# Addon-mapleCUx_HM-RFM69-RFM95-V10-016.net
KiCad netlist of a schematic drawn in EAGLE
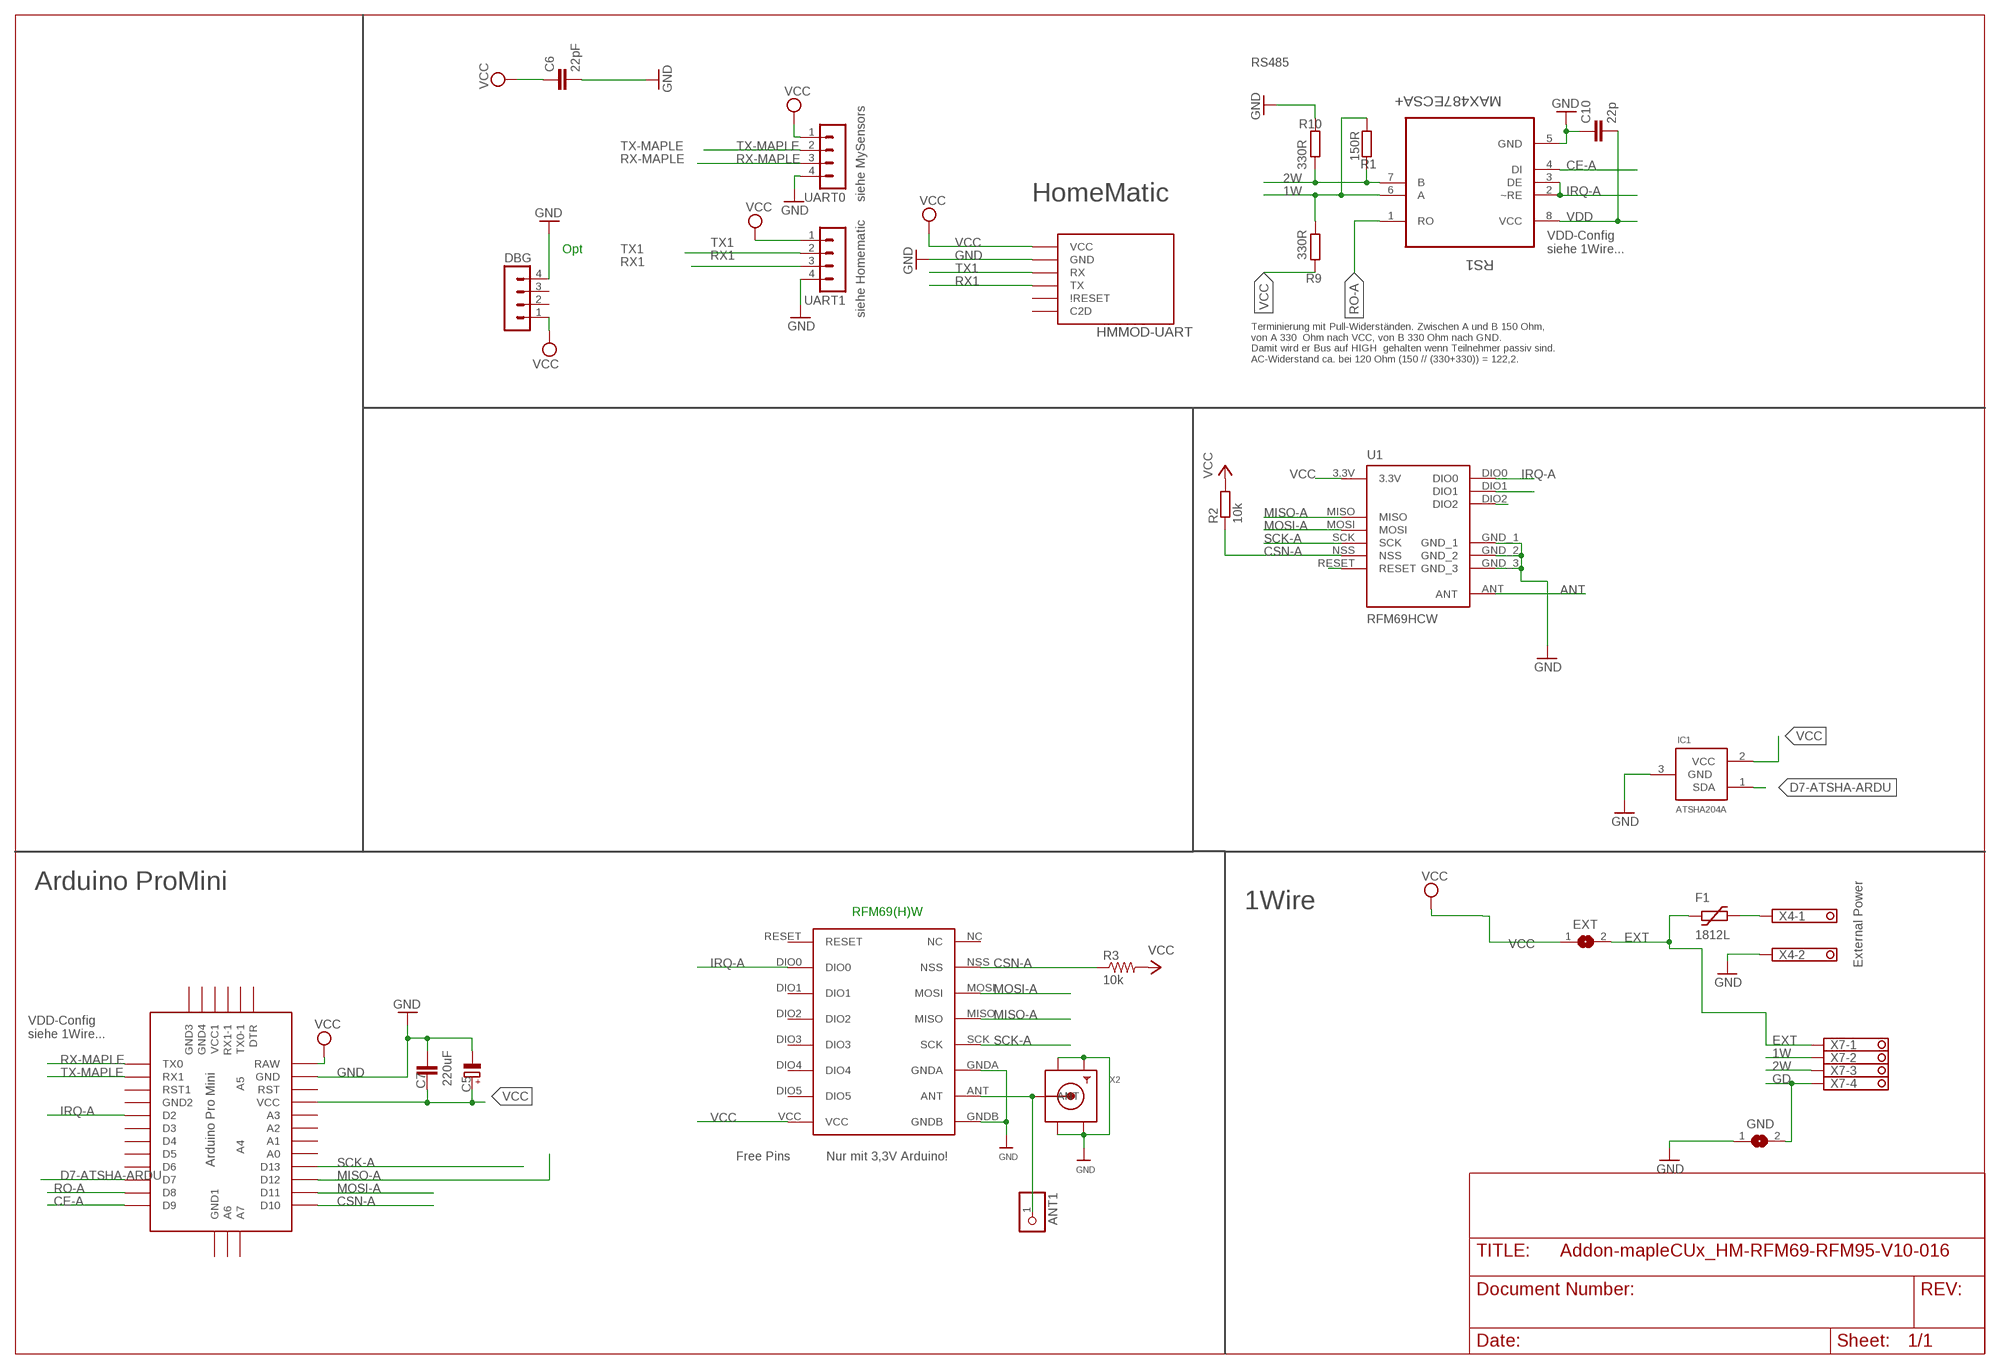
[diagram p0: schematic, sheet 1]

(export (version "E")
  (design (tool "Eeschema 10.0.6"))
  (components
    (comp (ref "ANT1")
      (value "PINHD-1X1")
      (footprint "eagle-import:1X01")
      (libsource (lib "eagle-import") (part "PINHD-1X1"))
    )
    (comp (ref "C5")
      (value "220uF")
      (footprint "eagle-import:E5-8,5")
      (libsource (lib "eagle-import") (part "CPOL-EUE5-8.5"))
    )
    (comp (ref "C6")
      (value "22pF")
      (footprint "eagle-import:C0805")
      (libsource (lib "eagle-import") (part "C-EUC0805"))
    )
    (comp (ref "C7")
      (value "C-EUC1812")
      (footprint "eagle-import:C1812")
      (libsource (lib "eagle-import") (part "C-EUC1812"))
    )
    (comp (ref "C10")
      (value "22p")
      (footprint "eagle-import:C0805")
      (libsource (lib "eagle-import") (part "C-EUC0805"))
    )
    (comp (ref "DBG")
      (value "MA04-1")
      (footprint "eagle-import:MA04-1")
      (libsource (lib "eagle-import") (part "MA04-1"))
    )
    (comp (ref "EXT") (value "SJ") (footprint "eagle-import:SJ") (libsource (lib "eagle-import") (part "SJ")))
    (comp (ref "F1")
      (value "1812L")
      (footprint "eagle-import:1812L")
      (libsource (lib "eagle-import") (part "1812L"))
    )
    (comp (ref "GND") (value "SJ") (footprint "eagle-import:SJ") (libsource (lib "eagle-import") (part "SJ")))
    (comp (ref "HMMOD-UART")
      (value "HM-MOD-UARTDIL")
      (footprint "eagle-import:HM-MOD-UART-DIL")
      (libsource (lib "eagle-import") (part "HM-MOD-UARTDIL"))
    )
    (comp (ref "IC1")
      (value "ATSHA204A")
      (footprint "eagle-import:SOT23")
      (libsource (lib "eagle-import") (part "ATSHA204A"))
    )
    (comp (ref "R1")
      (value "150R")
      (footprint "eagle-import:R0805")
      (libsource (lib "eagle-import") (part "R-EU_R0805"))
    )
    (comp (ref "R2")
      (value "10k")
      (footprint "eagle-import:M0805")
      (libsource (lib "eagle-import") (part "R-EU_M0805"))
    )
    (comp (ref "R3")
      (value "10k")
      (footprint "eagle-import:0805")
      (libsource (lib "eagle-import") (part "RESISTOR0805-RES"))
    )
    (comp (ref "R9")
      (value "330R")
      (footprint "eagle-import:R0805")
      (libsource (lib "eagle-import") (part "R-EU_R0805"))
    )
    (comp (ref "R10")
      (value "330R")
      (footprint "eagle-import:R0805")
      (libsource (lib "eagle-import") (part "R-EU_R0805"))
    )
    (comp (ref "RFM69W")
      (value "RFM69HW")
      (footprint "eagle-import:RFM")
      (libsource (lib "eagle-import") (part "RFM69HW"))
    )
    (comp (ref "RS1")
      (value "MAX487ECSA+")
      (footprint "eagle-import:SOIC127P600X175-8N")
      (libsource (lib "eagle-import") (part "MAX487ECSA+"))
    )
    (comp (ref "U$2")
      (value "ABK-PRO-MINI")
      (footprint "eagle-import:ABK-PRO-MINI")
      (libsource (lib "eagle-import") (part "ABK-PRO-MINI"))
    )
    (comp (ref "U1")
      (value "RFM69HCW")
      (footprint "eagle-import:RFM69HCW-XXXS2")
      (libsource (lib "eagle-import") (part "RFM69HCW"))
    )
    (comp (ref "UART0")
      (value "MA04-1")
      (footprint "eagle-import:MA04-1")
      (libsource (lib "eagle-import") (part "MA04-1"))
    )
    (comp (ref "UART1")
      (value "MA04-1")
      (footprint "eagle-import:MA04-1")
      (libsource (lib "eagle-import") (part "MA04-1"))
    )
    (comp (ref "X2")
      (value "SMACONNECTOR_EDGE")
      (footprint "eagle-import:SMA_EDGELAUNCH")
      (libsource (lib "eagle-import") (part "SMACONNECTOR_EDGE"))
    )
    (comp (ref "X4")
      (value "1751248")
      (footprint "eagle-import:1751248")
      (libsource (lib "eagle-import") (part "1751248"))
    )
    (comp (ref "X7")
      (value "1751264")
      (footprint "eagle-import:1751264")
      (libsource (lib "eagle-import") (part "1751264"))
    )
  )
  (nets
    (net (code "1") (name "/1W") (class "Default")
      (node (ref "R1") (pin "1") (pinfunction "1_1") (pintype "passive"))
      (node (ref "R9") (pin "2") (pinfunction "2_2") (pintype "passive"))
      (node (ref "RS1") (pin "6") (pinfunction "A_6") (pintype "bidirectional"))
      (node (ref "X7") (pin "2") (pinfunction "K_2") (pintype "passive"))
    )
    (net (code "2") (name "/2W") (class "Default")
      (node (ref "R1") (pin "2") (pinfunction "2_2") (pintype "passive"))
      (node (ref "R10") (pin "1") (pinfunction "1_1") (pintype "passive"))
      (node (ref "RS1") (pin "7") (pinfunction "B_7") (pintype "bidirectional"))
      (node (ref "X7") (pin "3") (pinfunction "K_3") (pintype "passive"))
    )
    (net (code "3") (name "/ANT") (class "Default")
      (node (ref "ANT1") (pin "1") (pinfunction "1_1") (pintype "passive"))
      (node (ref "RFM69W") (pin "ANT") (pinfunction "ANT_ANT") (pintype "bidirectional"))
      (node (ref "U1") (pin "ANT") (pinfunction "ANT_ANT") (pintype "passive"))
      (node (ref "X2") (pin "P") (pinfunction "ANT_P") (pintype "bidirectional"))
    )
    (net (code "4") (name "/CE-A") (class "Default")
      (node (ref "RS1") (pin "4") (pinfunction "DI_4") (pintype "input"))
      (node (ref "U$2") (pin "D9") (pinfunction "D9_D9") (pintype "bidirectional"))
    )
    (net (code "5") (name "/CSN-A") (class "Default")
      (node (ref "R2") (pin "1") (pinfunction "1_1") (pintype "passive"))
      (node (ref "R3") (pin "1") (pinfunction "1_1") (pintype "passive"))
      (node (ref "RFM69W") (pin "NSS") (pinfunction "NSS_NSS") (pintype "bidirectional"))
      (node (ref "U$2") (pin "D10") (pinfunction "D10_D10") (pintype "bidirectional"))
      (node (ref "U1") (pin "NSS") (pinfunction "NSS_NSS") (pintype "input"))
    )
    (net (code "6") (name "/EXT") (class "Default")
      (node (ref "EXT") (pin "2") (pinfunction "2_2") (pintype "passive"))
      (node (ref "F1") (pin "P$1") (pinfunction "1_P$1") (pintype "passive"))
      (node (ref "X7") (pin "1") (pinfunction "K_1") (pintype "passive"))
    )
    (net (code "7") (name "/GD") (class "Default")
      (node (ref "GND") (pin "2") (pinfunction "2_2") (pintype "passive"))
      (node (ref "X7") (pin "4") (pinfunction "K_4") (pintype "passive"))
    )
    (net (code "8") (name "/IRQ-A") (class "Default")
      (node (ref "RFM69W") (pin "DIO0") (pinfunction "DIO0_DIO0") (pintype "bidirectional"))
      (node (ref "RS1") (pin "2") (pinfunction "~{RE}_2") (pintype "input"))
      (node (ref "RS1") (pin "3") (pinfunction "DE_3") (pintype "input"))
      (node (ref "U$2") (pin "D2") (pinfunction "D2_D2") (pintype "bidirectional"))
      (node (ref "U1") (pin "DIO0") (pinfunction "DIO0_DIO0") (pintype "bidirectional"))
    )
    (net (code "9") (name "/MISO-A") (class "Default")
      (node (ref "RFM69W") (pin "MISO") (pinfunction "MISO_MISO") (pintype "bidirectional"))
      (node (ref "U$2") (pin "D12") (pinfunction "D12_D12") (pintype "bidirectional"))
      (node (ref "U1") (pin "MISO") (pinfunction "MISO_MISO") (pintype "bidirectional"))
    )
    (net (code "10") (name "/MOSI-A") (class "Default")
      (node (ref "RFM69W") (pin "MOSI") (pinfunction "MOSI_MOSI") (pintype "bidirectional"))
      (node (ref "U$2") (pin "D11") (pinfunction "D11_D11") (pintype "bidirectional"))
      (node (ref "U1") (pin "MOSI") (pinfunction "MOSI_MOSI") (pintype "input"))
    )
    (net (code "11") (name "/RX-MAPLE") (class "Default")
      (node (ref "U$2") (pin "TX0") (pinfunction "TX0_TX0") (pintype "bidirectional"))
      (node (ref "UART0") (pin "3") (pinfunction "3_3") (pintype "passive"))
    )
    (net (code "12") (name "/RX1") (class "Default")
      (node (ref "HMMOD-UART") (pin "5") (pinfunction "TX_5") (pintype "bidirectional"))
      (node (ref "UART1") (pin "3") (pinfunction "3_3") (pintype "passive"))
    )
    (net (code "13") (name "/SCK-A") (class "Default")
      (node (ref "RFM69W") (pin "SCK") (pinfunction "SCK_SCK") (pintype "bidirectional"))
      (node (ref "U$2") (pin "D13") (pinfunction "D13_D13") (pintype "bidirectional"))
      (node (ref "U1") (pin "SCK") (pinfunction "SCK_SCK") (pintype "input"))
    )
    (net (code "14") (name "/TX-MAPLE") (class "Default")
      (node (ref "U$2") (pin "RX1") (pinfunction "RX1_RX1") (pintype "bidirectional"))
      (node (ref "UART0") (pin "2") (pinfunction "2_2") (pintype "passive"))
    )
    (net (code "15") (name "/TX1") (class "Default")
      (node (ref "HMMOD-UART") (pin "6") (pinfunction "RX_6") (pintype "bidirectional"))
      (node (ref "UART1") (pin "2") (pinfunction "2_2") (pintype "passive"))
    )
    (net (code "16") (name "/VDD") (class "Default")
      (node (ref "C10") (pin "2") (pinfunction "2_2") (pintype "passive"))
      (node (ref "RS1") (pin "8") (pinfunction "VCC_8") (pintype "power_in"))
    )
    (net (code "17") (name "D7-ATSHA-ARDU") (class "Default")
      (node (ref "IC1") (pin "1") (pinfunction "SDA_1") (pintype "bidirectional"))
      (node (ref "U$2") (pin "D7") (pinfunction "D7_D7") (pintype "bidirectional"))
    )
    (net (code "18") (name "GND") (class "Default")
      (node (ref "C10") (pin "1") (pinfunction "1_1") (pintype "passive"))
      (node (ref "C5") (pin "-") (pinfunction "-_-") (pintype "passive"))
      (node (ref "C6") (pin "2") (pinfunction "2_2") (pintype "passive"))
      (node (ref "C7") (pin "1") (pinfunction "1_1") (pintype "passive"))
      (node (ref "DBG") (pin "4") (pinfunction "4_4") (pintype "passive"))
      (node (ref "GND") (pin "1") (pinfunction "1_1") (pintype "passive"))
      (node (ref "HMMOD-UART") (pin "2") (pinfunction "GND_2") (pintype "power_in"))
      (node (ref "IC1") (pin "3") (pinfunction "GND_3") (pintype "bidirectional"))
      (node (ref "R10") (pin "2") (pinfunction "2_2") (pintype "passive"))
      (node (ref "RFM69W") (pin "GNDA") (pinfunction "GNDA_GNDA") (pintype "bidirectional"))
      (node (ref "RFM69W") (pin "GNDB") (pinfunction "GNDB_GNDB") (pintype "bidirectional"))
      (node (ref "RS1") (pin "5") (pinfunction "GND_5") (pintype "passive"))
      (node (ref "U$2") (pin "GND") (pinfunction "GND_GND") (pintype "bidirectional"))
      (node (ref "U1") (pin "GND_1") (pinfunction "GND_1_GND_1") (pintype "power_in"))
      (node (ref "U1") (pin "GND_2") (pinfunction "GND_2_GND_2") (pintype "power_in"))
      (node (ref "U1") (pin "GND_3") (pinfunction "GND_3_GND_3") (pintype "power_in"))
      (node (ref "UART0") (pin "4") (pinfunction "4_4") (pintype "passive"))
      (node (ref "UART1") (pin "4") (pinfunction "4_4") (pintype "passive"))
      (node (ref "X2") (pin "GND@1") (pinfunction "GND4_GND@1") (pintype "power_in"))
      (node (ref "X2") (pin "GND@2") (pinfunction "GND3_GND@2") (pintype "power_in"))
      (node (ref "X2") (pin "GND@3") (pinfunction "GND2_GND@3") (pintype "power_in"))
      (node (ref "X2") (pin "GND@4") (pinfunction "GND1_GND@4") (pintype "power_in"))
      (node (ref "X4") (pin "2") (pinfunction "K_2") (pintype "passive"))
    )
    (net (code "19") (name "Net-(F1-2)") (class "Default")
      (node (ref "F1") (pin "P$2") (pinfunction "2_P$2") (pintype "passive"))
      (node (ref "X4") (pin "1") (pinfunction "K_1") (pintype "passive"))
    )
    (net (code "20") (name "RO-A") (class "Default")
      (node (ref "RS1") (pin "1") (pinfunction "RO_1") (pintype "output"))
      (node (ref "U$2") (pin "D8") (pinfunction "D8_D8") (pintype "bidirectional"))
    )
    (net (code "21") (name "VCC") (class "Default")
      (node (ref "C5") (pin "+") (pinfunction "+_+") (pintype "passive"))
      (node (ref "C6") (pin "1") (pinfunction "1_1") (pintype "passive"))
      (node (ref "C7") (pin "2") (pinfunction "2_2") (pintype "passive"))
      (node (ref "DBG") (pin "1") (pinfunction "1_1") (pintype "passive"))
      (node (ref "EXT") (pin "1") (pinfunction "1_1") (pintype "passive"))
      (node (ref "HMMOD-UART") (pin "1") (pinfunction "VCC_1") (pintype "power_in"))
      (node (ref "IC1") (pin "2") (pinfunction "VCC_2") (pintype "bidirectional"))
      (node (ref "R2") (pin "2") (pinfunction "2_2") (pintype "passive"))
      (node (ref "R3") (pin "2") (pinfunction "2_2") (pintype "passive"))
      (node (ref "R9") (pin "1") (pinfunction "1_1") (pintype "passive"))
      (node (ref "RFM69W") (pin "VCC") (pinfunction "VCC_VCC") (pintype "bidirectional"))
      (node (ref "U$2") (pin "RAW") (pinfunction "RAW_RAW") (pintype "bidirectional"))
      (node (ref "U$2") (pin "VCC") (pinfunction "VCC_VCC") (pintype "bidirectional"))
      (node (ref "U1") (pin "3.3V") (pinfunction "3.3V_3.3V") (pintype "power_in"))
      (node (ref "UART0") (pin "1") (pinfunction "1_1") (pintype "passive"))
      (node (ref "UART1") (pin "1") (pinfunction "1_1") (pintype "passive"))
    )
    (net (code "22") (name "unconnected-(DBG-Pad2)") (class "Default")
      (node (ref "DBG") (pin "2") (pinfunction "2_2") (pintype "passive"))
    )
    (net (code "23") (name "unconnected-(DBG-Pad3)") (class "Default")
      (node (ref "DBG") (pin "3") (pinfunction "3_3") (pintype "passive"))
    )
    (net (code "24") (name "unconnected-(HMMOD-UART-C2D-Pad3)") (class "Default")
      (node (ref "HMMOD-UART") (pin "3") (pinfunction "C2D_3") (pintype "bidirectional"))
    )
    (net (code "25") (name "unconnected-(HMMOD-UART-\\~{RESET}-Pad4)") (class "Default")
      (node (ref "HMMOD-UART") (pin "4") (pinfunction "\\~{RESET}_4") (pintype "bidirectional"))
    )
    (net (code "26") (name "unconnected-(RFM69W-PadDIO1)") (class "Default")
      (node (ref "RFM69W") (pin "DIO1") (pinfunction "DIO1_DIO1") (pintype "bidirectional"))
    )
    (net (code "27") (name "unconnected-(RFM69W-PadDIO2)") (class "Default")
      (node (ref "RFM69W") (pin "DIO2") (pinfunction "DIO2_DIO2") (pintype "bidirectional"))
    )
    (net (code "28") (name "unconnected-(RFM69W-PadDIO3)") (class "Default")
      (node (ref "RFM69W") (pin "DIO3") (pinfunction "DIO3_DIO3") (pintype "bidirectional"))
    )
    (net (code "29") (name "unconnected-(RFM69W-PadDIO4)") (class "Default")
      (node (ref "RFM69W") (pin "DIO4") (pinfunction "DIO4_DIO4") (pintype "bidirectional"))
    )
    (net (code "30") (name "unconnected-(RFM69W-PadDIO5)") (class "Default")
      (node (ref "RFM69W") (pin "DIO5") (pinfunction "DIO5_DIO5") (pintype "bidirectional"))
    )
    (net (code "31") (name "unconnected-(RFM69W-PadNC)") (class "Default")
      (node (ref "RFM69W") (pin "NC") (pinfunction "NC_NC") (pintype "bidirectional"))
    )
    (net (code "32") (name "unconnected-(RFM69W-PadRESET)") (class "Default")
      (node (ref "RFM69W") (pin "RESET") (pinfunction "RESET_RESET") (pintype "bidirectional"))
    )
    (net (code "33") (name "unconnected-(U$2-GND1-PadGND4)") (class "Default")
      (node (ref "U$2") (pin "GND4") (pinfunction "GND1_GND4") (pintype "bidirectional"))
    )
    (net (code "34") (name "unconnected-(U$2-GND2-PadGND1)") (class "Default")
      (node (ref "U$2") (pin "GND1") (pinfunction "GND2_GND1") (pintype "bidirectional"))
    )
    (net (code "35") (name "unconnected-(U$2-GND3-PadGND2)") (class "Default")
      (node (ref "U$2") (pin "GND2") (pinfunction "GND3_GND2") (pintype "bidirectional"))
    )
    (net (code "36") (name "unconnected-(U$2-GND4-PadGND3)") (class "Default")
      (node (ref "U$2") (pin "GND3") (pinfunction "GND4_GND3") (pintype "bidirectional"))
    )
    (net (code "37") (name "unconnected-(U$2-PadA0)") (class "Default")
      (node (ref "U$2") (pin "A0") (pinfunction "A0_A0") (pintype "bidirectional"))
    )
    (net (code "38") (name "unconnected-(U$2-PadA1)") (class "Default")
      (node (ref "U$2") (pin "A1") (pinfunction "A1_A1") (pintype "bidirectional"))
    )
    (net (code "39") (name "unconnected-(U$2-PadA2)") (class "Default")
      (node (ref "U$2") (pin "A2") (pinfunction "A2_A2") (pintype "bidirectional"))
    )
    (net (code "40") (name "unconnected-(U$2-PadA3)") (class "Default")
      (node (ref "U$2") (pin "A3") (pinfunction "A3_A3") (pintype "bidirectional"))
    )
    (net (code "41") (name "unconnected-(U$2-PadA4)") (class "Default")
      (node (ref "U$2") (pin "A4") (pinfunction "A4_A4") (pintype "bidirectional"))
    )
    (net (code "42") (name "unconnected-(U$2-PadA5)") (class "Default")
      (node (ref "U$2") (pin "A5") (pinfunction "A5_A5") (pintype "bidirectional"))
    )
    (net (code "43") (name "unconnected-(U$2-PadA6)") (class "Default")
      (node (ref "U$2") (pin "A6") (pinfunction "A6_A6") (pintype "bidirectional"))
    )
    (net (code "44") (name "unconnected-(U$2-PadA7)") (class "Default")
      (node (ref "U$2") (pin "A7") (pinfunction "A7_A7") (pintype "bidirectional"))
    )
    (net (code "45") (name "unconnected-(U$2-PadD3)") (class "Default")
      (node (ref "U$2") (pin "D3") (pinfunction "D3_D3") (pintype "bidirectional"))
    )
    (net (code "46") (name "unconnected-(U$2-PadD4)") (class "Default")
      (node (ref "U$2") (pin "D4") (pinfunction "D4_D4") (pintype "bidirectional"))
    )
    (net (code "47") (name "unconnected-(U$2-PadD5)") (class "Default")
      (node (ref "U$2") (pin "D5") (pinfunction "D5_D5") (pintype "bidirectional"))
    )
    (net (code "48") (name "unconnected-(U$2-PadD6)") (class "Default")
      (node (ref "U$2") (pin "D6") (pinfunction "D6_D6") (pintype "bidirectional"))
    )
    (net (code "49") (name "unconnected-(U$2-PadDTR)") (class "Default")
      (node (ref "U$2") (pin "DTR") (pinfunction "DTR_DTR") (pintype "bidirectional"))
    )
    (net (code "50") (name "unconnected-(U$2-PadRST)") (class "Default")
      (node (ref "U$2") (pin "RST") (pinfunction "RST_RST") (pintype "bidirectional"))
    )
    (net (code "51") (name "unconnected-(U$2-PadRST1)") (class "Default")
      (node (ref "U$2") (pin "RST1") (pinfunction "RST1_RST1") (pintype "bidirectional"))
    )
    (net (code "52") (name "unconnected-(U$2-PadRX1-1)") (class "Default")
      (node (ref "U$2") (pin "RX1-1") (pinfunction "RX1-1_RX1-1") (pintype "bidirectional"))
    )
    (net (code "53") (name "unconnected-(U$2-PadTX0-1)") (class "Default")
      (node (ref "U$2") (pin "TX0-1") (pinfunction "TX0-1_TX0-1") (pintype "bidirectional"))
    )
    (net (code "54") (name "unconnected-(U$2-PadVCC1)") (class "Default")
      (node (ref "U$2") (pin "VCC1") (pinfunction "VCC1_VCC1") (pintype "bidirectional"))
    )
    (net (code "55") (name "unconnected-(U1-PadDIO1)") (class "Default")
      (node (ref "U1") (pin "DIO1") (pinfunction "DIO1_DIO1") (pintype "bidirectional"))
    )
    (net (code "56") (name "unconnected-(U1-PadDIO2)") (class "Default")
      (node (ref "U1") (pin "DIO2") (pinfunction "DIO2_DIO2") (pintype "bidirectional"))
    )
    (net (code "57") (name "unconnected-(U1-PadRESET)") (class "Default")
      (node (ref "U1") (pin "RESET") (pinfunction "RESET_RESET") (pintype "input"))
    )
  )
)
